# biv2-LRTP_1a.net
KiCad netlist of a schematic drawn in Altium Designer
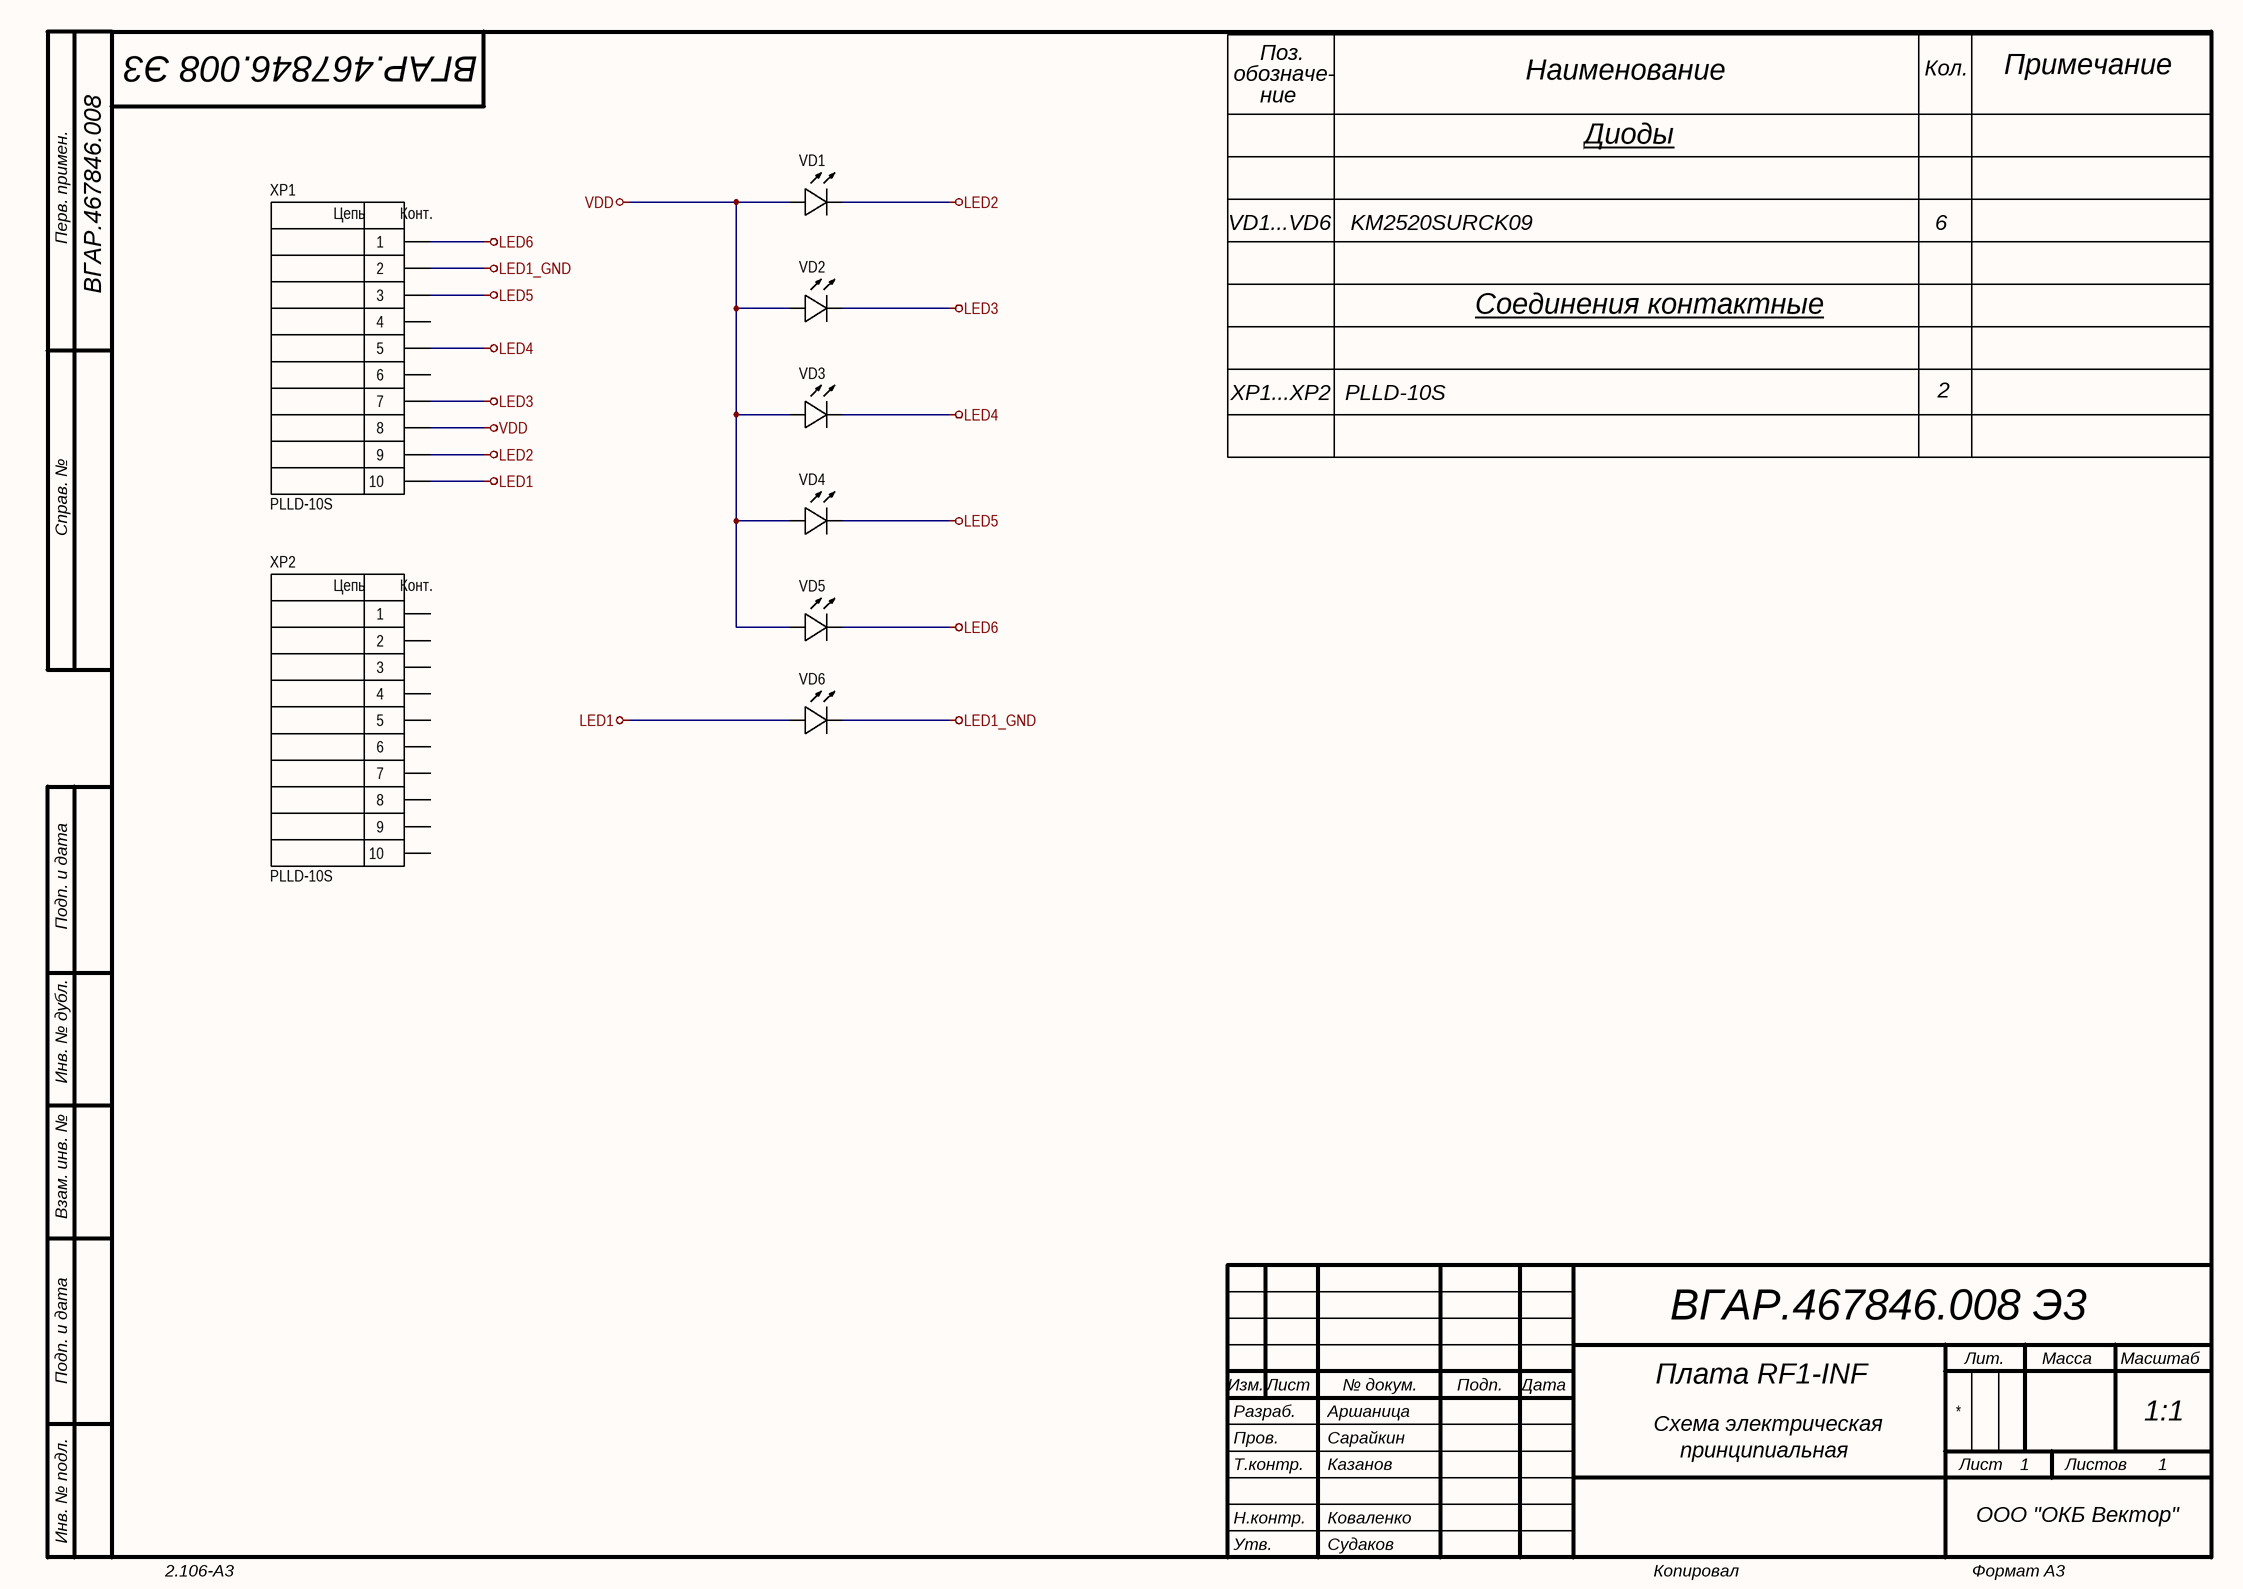
[diagram p0: biv2-LRTP_1a.SchDoc]

(export (version "E")
  (design (tool "Eeschema 10.0.6"))
  (components
    (comp (ref "VD1")
      (value "KM2520SURCK09")
      (footprint "KM2520SURCK09")
      (description "LED")
      (libsource (lib "Kingbright LED") (part "KM2520SURCK09"))
    )
    (comp (ref "VD2")
      (value "KM2520SURCK09")
      (footprint "KM2520SURCK09")
      (description "LED")
      (libsource (lib "Kingbright LED") (part "KM2520SURCK09"))
    )
    (comp (ref "VD3")
      (value "KM2520SURCK09")
      (footprint "KM2520SURCK09")
      (description "LED")
      (libsource (lib "Kingbright LED") (part "KM2520SURCK09"))
    )
    (comp (ref "VD4")
      (value "KM2520SURCK09")
      (footprint "KM2520SURCK09")
      (description "LED")
      (libsource (lib "Kingbright LED") (part "KM2520SURCK09"))
    )
    (comp (ref "VD5")
      (value "KM2520SURCK09")
      (footprint "KM2520SURCK09")
      (description "LED")
      (libsource (lib "Kingbright LED") (part "KM2520SURCK09"))
    )
    (comp (ref "VD6")
      (value "KM2520SURCK09")
      (footprint "KM2520SURCK09")
      (description "LED")
      (libsource (lib "Kingbright LED") (part "KM2520SURCK09"))
    )
    (comp (ref "XP1")
      (value "PLLD-10S")
      (footprint "CON: PLLD-10S")
      (description "Step 1.27")
      (libsource (lib "connector") (part "PLLD-10S"))
    )
    (comp (ref "XP2")
      (value "PLLD-10S")
      (footprint "CON: PLLD-10S")
      (description "Step 1.27")
      (libsource (lib "connector") (part "PLLD-10S"))
    )
  )
  (nets
    (net (code "1") (name "LED1") (class "Default")
      (node (ref "VD6") (pin "1") (pinfunction "A_1") (pintype "passive"))
      (node (ref "XP1") (pin "10") (pinfunction "10_10") (pintype "passive"))
    )
    (net (code "2") (name "LED1_GND") (class "Default")
      (node (ref "VD6") (pin "2") (pinfunction "K_2") (pintype "passive"))
      (node (ref "XP1") (pin "2") (pinfunction "2_2") (pintype "passive"))
    )
    (net (code "3") (name "LED2") (class "Default")
      (node (ref "VD1") (pin "2") (pinfunction "K_2") (pintype "passive"))
      (node (ref "XP1") (pin "9") (pinfunction "9_9") (pintype "passive"))
    )
    (net (code "4") (name "LED3") (class "Default")
      (node (ref "VD2") (pin "2") (pinfunction "K_2") (pintype "passive"))
      (node (ref "XP1") (pin "7") (pinfunction "7_7") (pintype "passive"))
    )
    (net (code "5") (name "LED4") (class "Default")
      (node (ref "VD3") (pin "2") (pinfunction "K_2") (pintype "passive"))
      (node (ref "XP1") (pin "5") (pinfunction "5_5") (pintype "passive"))
    )
    (net (code "6") (name "LED5") (class "Default")
      (node (ref "VD4") (pin "2") (pinfunction "K_2") (pintype "passive"))
      (node (ref "XP1") (pin "3") (pinfunction "3_3") (pintype "passive"))
    )
    (net (code "7") (name "LED6") (class "Default")
      (node (ref "VD5") (pin "2") (pinfunction "K_2") (pintype "passive"))
      (node (ref "XP1") (pin "1") (pinfunction "1_1") (pintype "passive"))
    )
    (net (code "8") (name "VDD") (class "Default")
      (node (ref "VD1") (pin "1") (pinfunction "A_1") (pintype "passive"))
      (node (ref "VD2") (pin "1") (pinfunction "A_1") (pintype "passive"))
      (node (ref "VD3") (pin "1") (pinfunction "A_1") (pintype "passive"))
      (node (ref "VD4") (pin "1") (pinfunction "A_1") (pintype "passive"))
      (node (ref "VD5") (pin "1") (pinfunction "A_1") (pintype "passive"))
      (node (ref "XP1") (pin "8") (pinfunction "8_8") (pintype "passive"))
    )
    (net (code "9") (name "unconnected-(XP1-Pad4)") (class "Default")
      (node (ref "XP1") (pin "4") (pinfunction "4_4") (pintype "passive"))
    )
    (net (code "10") (name "unconnected-(XP1-Pad6)") (class "Default")
      (node (ref "XP1") (pin "6") (pinfunction "6_6") (pintype "passive"))
    )
    (net (code "11") (name "unconnected-(XP2-Pad1)") (class "Default")
      (node (ref "XP2") (pin "1") (pinfunction "1_1") (pintype "passive"))
    )
    (net (code "12") (name "unconnected-(XP2-Pad2)") (class "Default")
      (node (ref "XP2") (pin "2") (pinfunction "2_2") (pintype "passive"))
    )
    (net (code "13") (name "unconnected-(XP2-Pad3)") (class "Default")
      (node (ref "XP2") (pin "3") (pinfunction "3_3") (pintype "passive"))
    )
    (net (code "14") (name "unconnected-(XP2-Pad4)") (class "Default")
      (node (ref "XP2") (pin "4") (pinfunction "4_4") (pintype "passive"))
    )
    (net (code "15") (name "unconnected-(XP2-Pad5)") (class "Default")
      (node (ref "XP2") (pin "5") (pinfunction "5_5") (pintype "passive"))
    )
    (net (code "16") (name "unconnected-(XP2-Pad6)") (class "Default")
      (node (ref "XP2") (pin "6") (pinfunction "6_6") (pintype "passive"))
    )
    (net (code "17") (name "unconnected-(XP2-Pad7)") (class "Default")
      (node (ref "XP2") (pin "7") (pinfunction "7_7") (pintype "passive"))
    )
    (net (code "18") (name "unconnected-(XP2-Pad8)") (class "Default")
      (node (ref "XP2") (pin "8") (pinfunction "8_8") (pintype "passive"))
    )
    (net (code "19") (name "unconnected-(XP2-Pad9)") (class "Default")
      (node (ref "XP2") (pin "9") (pinfunction "9_9") (pintype "passive"))
    )
    (net (code "20") (name "unconnected-(XP2-Pad10)") (class "Default")
      (node (ref "XP2") (pin "10") (pinfunction "10_10") (pintype "passive"))
    )
  )
)
